# Nixie.net
KiCad netlist of a schematic drawn in EAGLE
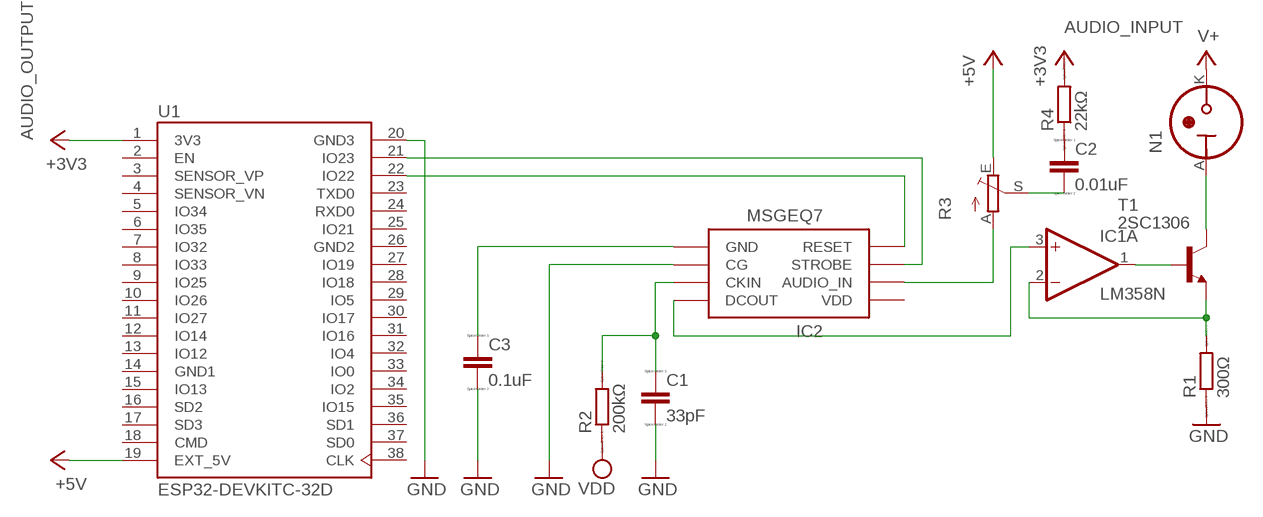
[diagram p0: schematic, sheet 1]

(export (version "E")
  (design (tool "Eeschema 10.0.6"))
  (components
    (comp (ref "C1")
      (value "33pF")
      (footprint "eagle-import:C0805")
      (libsource (lib "eagle-import") (part "C"))
    )
    (comp (ref "C2")
      (value "0.01uF")
      (footprint "eagle-import:C0805")
      (libsource (lib "eagle-import") (part "C"))
    )
    (comp (ref "C3")
      (value "0.1uF")
      (footprint "eagle-import:C0805")
      (libsource (lib "eagle-import") (part "C"))
    )
    (comp (ref "IC1")
      (value "LM358N")
      (footprint "eagle-import:DIL08")
      (libsource (lib "eagle-import") (part "LM358N"))
    )
    (comp (ref "IC2")
      (value "MSGEQ7DIL")
      (footprint "eagle-import:DIL-08")
      (fields (field (name "MF") "Mixed Signal Integration") (field (name "MP") "MSGEQ7"))
      (libsource (lib "eagle-import") (part "MSGEQ7DIL"))
    )
    (comp (ref "N1")
      (value "IN-9")
      (footprint "eagle-import:IN-9")
      (libsource (lib "eagle-import") (part "IN-9"))
    )
    (comp (ref "R1")
      (value "300Ω")
      (footprint "eagle-import:R0805")
      (libsource (lib "eagle-import") (part "R"))
    )
    (comp (ref "R2")
      (value "200kΩ")
      (footprint "eagle-import:R0805")
      (libsource (lib "eagle-import") (part "R"))
    )
    (comp (ref "R3")
      (value "TRIM_EU-B25P")
      (footprint "eagle-import:B25P")
      (libsource (lib "eagle-import") (part "TRIM_EU-B25P"))
    )
    (comp (ref "R4")
      (value "22kΩ")
      (footprint "eagle-import:R0805")
      (libsource (lib "eagle-import") (part "R"))
    )
    (comp (ref "T1")
      (value "2SC1306")
      (footprint "eagle-import:TO220BV")
      (libsource (lib "eagle-import") (part "2SC1306"))
    )
    (comp (ref "U1")
      (value "ESP32-DEVKITC-32D")
      (footprint "eagle-import:MODULE_ESP32-DEVKITC-32D")
      (fields (field (name "MF") "Espressif Systems"))
      (libsource (lib "eagle-import") (part "ESP32-DEVKITC-32D"))
    )
  )
  (nets
    (net (code "1") (name "+3V3") (class "Default")
      (node (ref "R4") (pin "2") (pinfunction "2_2") (pintype "passive"))
      (node (ref "U1") (pin "1") (pinfunction "3V3_1") (pintype "power_in"))
    )
    (net (code "2") (name "+5V") (class "Default")
      (node (ref "R3") (pin "E") (pinfunction "E_E") (pintype "passive"))
      (node (ref "U1") (pin "19") (pinfunction "EXT_5V_19") (pintype "power_in"))
    )
    (net (code "3") (name "/GND1") (class "Default")
      (node (ref "U1") (pin "14") (pinfunction "GND1_14") (pintype "power_in"))
    )
    (net (code "4") (name "/GND2") (class "Default")
      (node (ref "U1") (pin "26") (pinfunction "GND2_26") (pintype "power_in"))
    )
    (net (code "5") (name "GND") (class "Default")
      (node (ref "C1") (pin "2") (pinfunction "2_2") (pintype "passive"))
      (node (ref "C3") (pin "2") (pinfunction "2_2") (pintype "passive"))
      (node (ref "IC2") (pin "6") (pinfunction "CG_6") (pintype "bidirectional"))
      (node (ref "R1") (pin "1") (pinfunction "1_1") (pintype "passive"))
      (node (ref "U1") (pin "20") (pinfunction "GND3_20") (pintype "power_in"))
    )
    (net (code "6") (name "Net-(C2-Pad1)") (class "Default")
      (node (ref "C2") (pin "1") (pinfunction "1_1") (pintype "passive"))
      (node (ref "R4") (pin "1") (pinfunction "1_1") (pintype "passive"))
    )
    (net (code "7") (name "Net-(C2-Pad2)") (class "Default")
      (node (ref "C2") (pin "2") (pinfunction "2_2") (pintype "passive"))
      (node (ref "R3") (pin "S") (pinfunction "S_S") (pintype "passive"))
    )
    (net (code "8") (name "Net-(IC1A-+IN)") (class "Default")
      (node (ref "IC1") (pin "3") (pinfunction "+IN_3") (pintype "input"))
      (node (ref "IC2") (pin "3") (pinfunction "DCOUT_3") (pintype "bidirectional"))
    )
    (net (code "9") (name "Net-(IC1A--IN)") (class "Default")
      (node (ref "IC1") (pin "2") (pinfunction "-IN_2") (pintype "input"))
      (node (ref "R1") (pin "2") (pinfunction "2_2") (pintype "passive"))
      (node (ref "T1") (pin "3") (pinfunction "E_3") (pintype "passive"))
    )
    (net (code "10") (name "Net-(IC1A-OUT)") (class "Default")
      (node (ref "IC1") (pin "1") (pinfunction "OUT_1") (pintype "output"))
      (node (ref "T1") (pin "1") (pinfunction "B_1") (pintype "passive"))
    )
    (net (code "11") (name "Net-(IC2-AUDIO_IN)") (class "Default")
      (node (ref "IC2") (pin "5") (pinfunction "AUDIO_IN_5") (pintype "input"))
      (node (ref "R3") (pin "A") (pinfunction "A_A") (pintype "passive"))
    )
    (net (code "12") (name "Net-(IC2-CKIN)") (class "Default")
      (node (ref "C1") (pin "1") (pinfunction "1_1") (pintype "passive"))
      (node (ref "IC2") (pin "8") (pinfunction "CKIN_8") (pintype "bidirectional"))
      (node (ref "R2") (pin "2") (pinfunction "2_2") (pintype "passive"))
    )
    (net (code "13") (name "Net-(IC2-GND)") (class "Default")
      (node (ref "C3") (pin "1") (pinfunction "1_1") (pintype "passive"))
      (node (ref "IC2") (pin "2") (pinfunction "GND_2") (pintype "bidirectional"))
    )
    (net (code "14") (name "Net-(IC2-RESET)") (class "Default")
      (node (ref "IC2") (pin "7") (pinfunction "RESET_7") (pintype "input"))
      (node (ref "U1") (pin "22") (pinfunction "IO22_22") (pintype "bidirectional"))
    )
    (net (code "15") (name "Net-(IC2-STROBE)") (class "Default")
      (node (ref "IC2") (pin "4") (pinfunction "STROBE_4") (pintype "input"))
      (node (ref "U1") (pin "21") (pinfunction "IO23_21") (pintype "bidirectional"))
    )
    (net (code "16") (name "Net-(T1-C)") (class "Default")
      (node (ref "N1") (pin "A") (pinfunction "A_A") (pintype "bidirectional"))
      (node (ref "T1") (pin "2") (pinfunction "C_2") (pintype "passive"))
    )
    (net (code "17") (name "V+") (class "Default")
      (node (ref "N1") (pin "K") (pinfunction "K_K") (pintype "bidirectional"))
    )
    (net (code "18") (name "VDD") (class "Default")
      (node (ref "R2") (pin "1") (pinfunction "1_1") (pintype "passive"))
    )
    (net (code "19") (name "unconnected-(IC2-VDD-Pad1)") (class "Default")
      (node (ref "IC2") (pin "1") (pinfunction "VDD_1") (pintype "input"))
    )
    (net (code "20") (name "unconnected-(U1-CLK-Pad38)") (class "Default")
      (node (ref "U1") (pin "38") (pinfunction "CLK_38") (pintype "input"))
    )
    (net (code "21") (name "unconnected-(U1-CMD-Pad18)") (class "Default")
      (node (ref "U1") (pin "18") (pinfunction "CMD_18") (pintype "bidirectional"))
    )
    (net (code "22") (name "unconnected-(U1-EN-Pad2)") (class "Default")
      (node (ref "U1") (pin "2") (pinfunction "EN_2") (pintype "input"))
    )
    (net (code "23") (name "unconnected-(U1-IO0-Pad33)") (class "Default")
      (node (ref "U1") (pin "33") (pinfunction "IO0_33") (pintype "bidirectional"))
    )
    (net (code "24") (name "unconnected-(U1-IO2-Pad34)") (class "Default")
      (node (ref "U1") (pin "34") (pinfunction "IO2_34") (pintype "bidirectional"))
    )
    (net (code "25") (name "unconnected-(U1-IO4-Pad32)") (class "Default")
      (node (ref "U1") (pin "32") (pinfunction "IO4_32") (pintype "bidirectional"))
    )
    (net (code "26") (name "unconnected-(U1-IO5-Pad29)") (class "Default")
      (node (ref "U1") (pin "29") (pinfunction "IO5_29") (pintype "bidirectional"))
    )
    (net (code "27") (name "unconnected-(U1-IO12-Pad13)") (class "Default")
      (node (ref "U1") (pin "13") (pinfunction "IO12_13") (pintype "bidirectional"))
    )
    (net (code "28") (name "unconnected-(U1-IO13-Pad15)") (class "Default")
      (node (ref "U1") (pin "15") (pinfunction "IO13_15") (pintype "bidirectional"))
    )
    (net (code "29") (name "unconnected-(U1-IO14-Pad12)") (class "Default")
      (node (ref "U1") (pin "12") (pinfunction "IO14_12") (pintype "bidirectional"))
    )
    (net (code "30") (name "unconnected-(U1-IO15-Pad35)") (class "Default")
      (node (ref "U1") (pin "35") (pinfunction "IO15_35") (pintype "bidirectional"))
    )
    (net (code "31") (name "unconnected-(U1-IO16-Pad31)") (class "Default")
      (node (ref "U1") (pin "31") (pinfunction "IO16_31") (pintype "bidirectional"))
    )
    (net (code "32") (name "unconnected-(U1-IO17-Pad30)") (class "Default")
      (node (ref "U1") (pin "30") (pinfunction "IO17_30") (pintype "bidirectional"))
    )
    (net (code "33") (name "unconnected-(U1-IO18-Pad28)") (class "Default")
      (node (ref "U1") (pin "28") (pinfunction "IO18_28") (pintype "bidirectional"))
    )
    (net (code "34") (name "unconnected-(U1-IO19-Pad27)") (class "Default")
      (node (ref "U1") (pin "27") (pinfunction "IO19_27") (pintype "bidirectional"))
    )
    (net (code "35") (name "unconnected-(U1-IO21-Pad25)") (class "Default")
      (node (ref "U1") (pin "25") (pinfunction "IO21_25") (pintype "bidirectional"))
    )
    (net (code "36") (name "unconnected-(U1-IO25-Pad9)") (class "Default")
      (node (ref "U1") (pin "9") (pinfunction "IO25_9") (pintype "bidirectional"))
    )
    (net (code "37") (name "unconnected-(U1-IO26-Pad10)") (class "Default")
      (node (ref "U1") (pin "10") (pinfunction "IO26_10") (pintype "bidirectional"))
    )
    (net (code "38") (name "unconnected-(U1-IO27-Pad11)") (class "Default")
      (node (ref "U1") (pin "11") (pinfunction "IO27_11") (pintype "bidirectional"))
    )
    (net (code "39") (name "unconnected-(U1-IO32-Pad7)") (class "Default")
      (node (ref "U1") (pin "7") (pinfunction "IO32_7") (pintype "bidirectional"))
    )
    (net (code "40") (name "unconnected-(U1-IO33-Pad8)") (class "Default")
      (node (ref "U1") (pin "8") (pinfunction "IO33_8") (pintype "bidirectional"))
    )
    (net (code "41") (name "unconnected-(U1-IO34-Pad5)") (class "Default")
      (node (ref "U1") (pin "5") (pinfunction "IO34_5") (pintype "bidirectional"))
    )
    (net (code "42") (name "unconnected-(U1-IO35-Pad6)") (class "Default")
      (node (ref "U1") (pin "6") (pinfunction "IO35_6") (pintype "bidirectional"))
    )
    (net (code "43") (name "unconnected-(U1-RXD0-Pad24)") (class "Default")
      (node (ref "U1") (pin "24") (pinfunction "RXD0_24") (pintype "input"))
    )
    (net (code "44") (name "unconnected-(U1-SD0-Pad37)") (class "Default")
      (node (ref "U1") (pin "37") (pinfunction "SD0_37") (pintype "bidirectional"))
    )
    (net (code "45") (name "unconnected-(U1-SD1-Pad36)") (class "Default")
      (node (ref "U1") (pin "36") (pinfunction "SD1_36") (pintype "bidirectional"))
    )
    (net (code "46") (name "unconnected-(U1-SD2-Pad16)") (class "Default")
      (node (ref "U1") (pin "16") (pinfunction "SD2_16") (pintype "bidirectional"))
    )
    (net (code "47") (name "unconnected-(U1-SD3-Pad17)") (class "Default")
      (node (ref "U1") (pin "17") (pinfunction "SD3_17") (pintype "bidirectional"))
    )
    (net (code "48") (name "unconnected-(U1-SENSOR_VN-Pad4)") (class "Default")
      (node (ref "U1") (pin "4") (pinfunction "SENSOR_VN_4") (pintype "input"))
    )
    (net (code "49") (name "unconnected-(U1-SENSOR_VP-Pad3)") (class "Default")
      (node (ref "U1") (pin "3") (pinfunction "SENSOR_VP_3") (pintype "input"))
    )
    (net (code "50") (name "unconnected-(U1-TXD0-Pad23)") (class "Default")
      (node (ref "U1") (pin "23") (pinfunction "TXD0_23") (pintype "output"))
    )
  )
)
